# MSP.net
KiCad netlist of a schematic drawn in Altium Designer
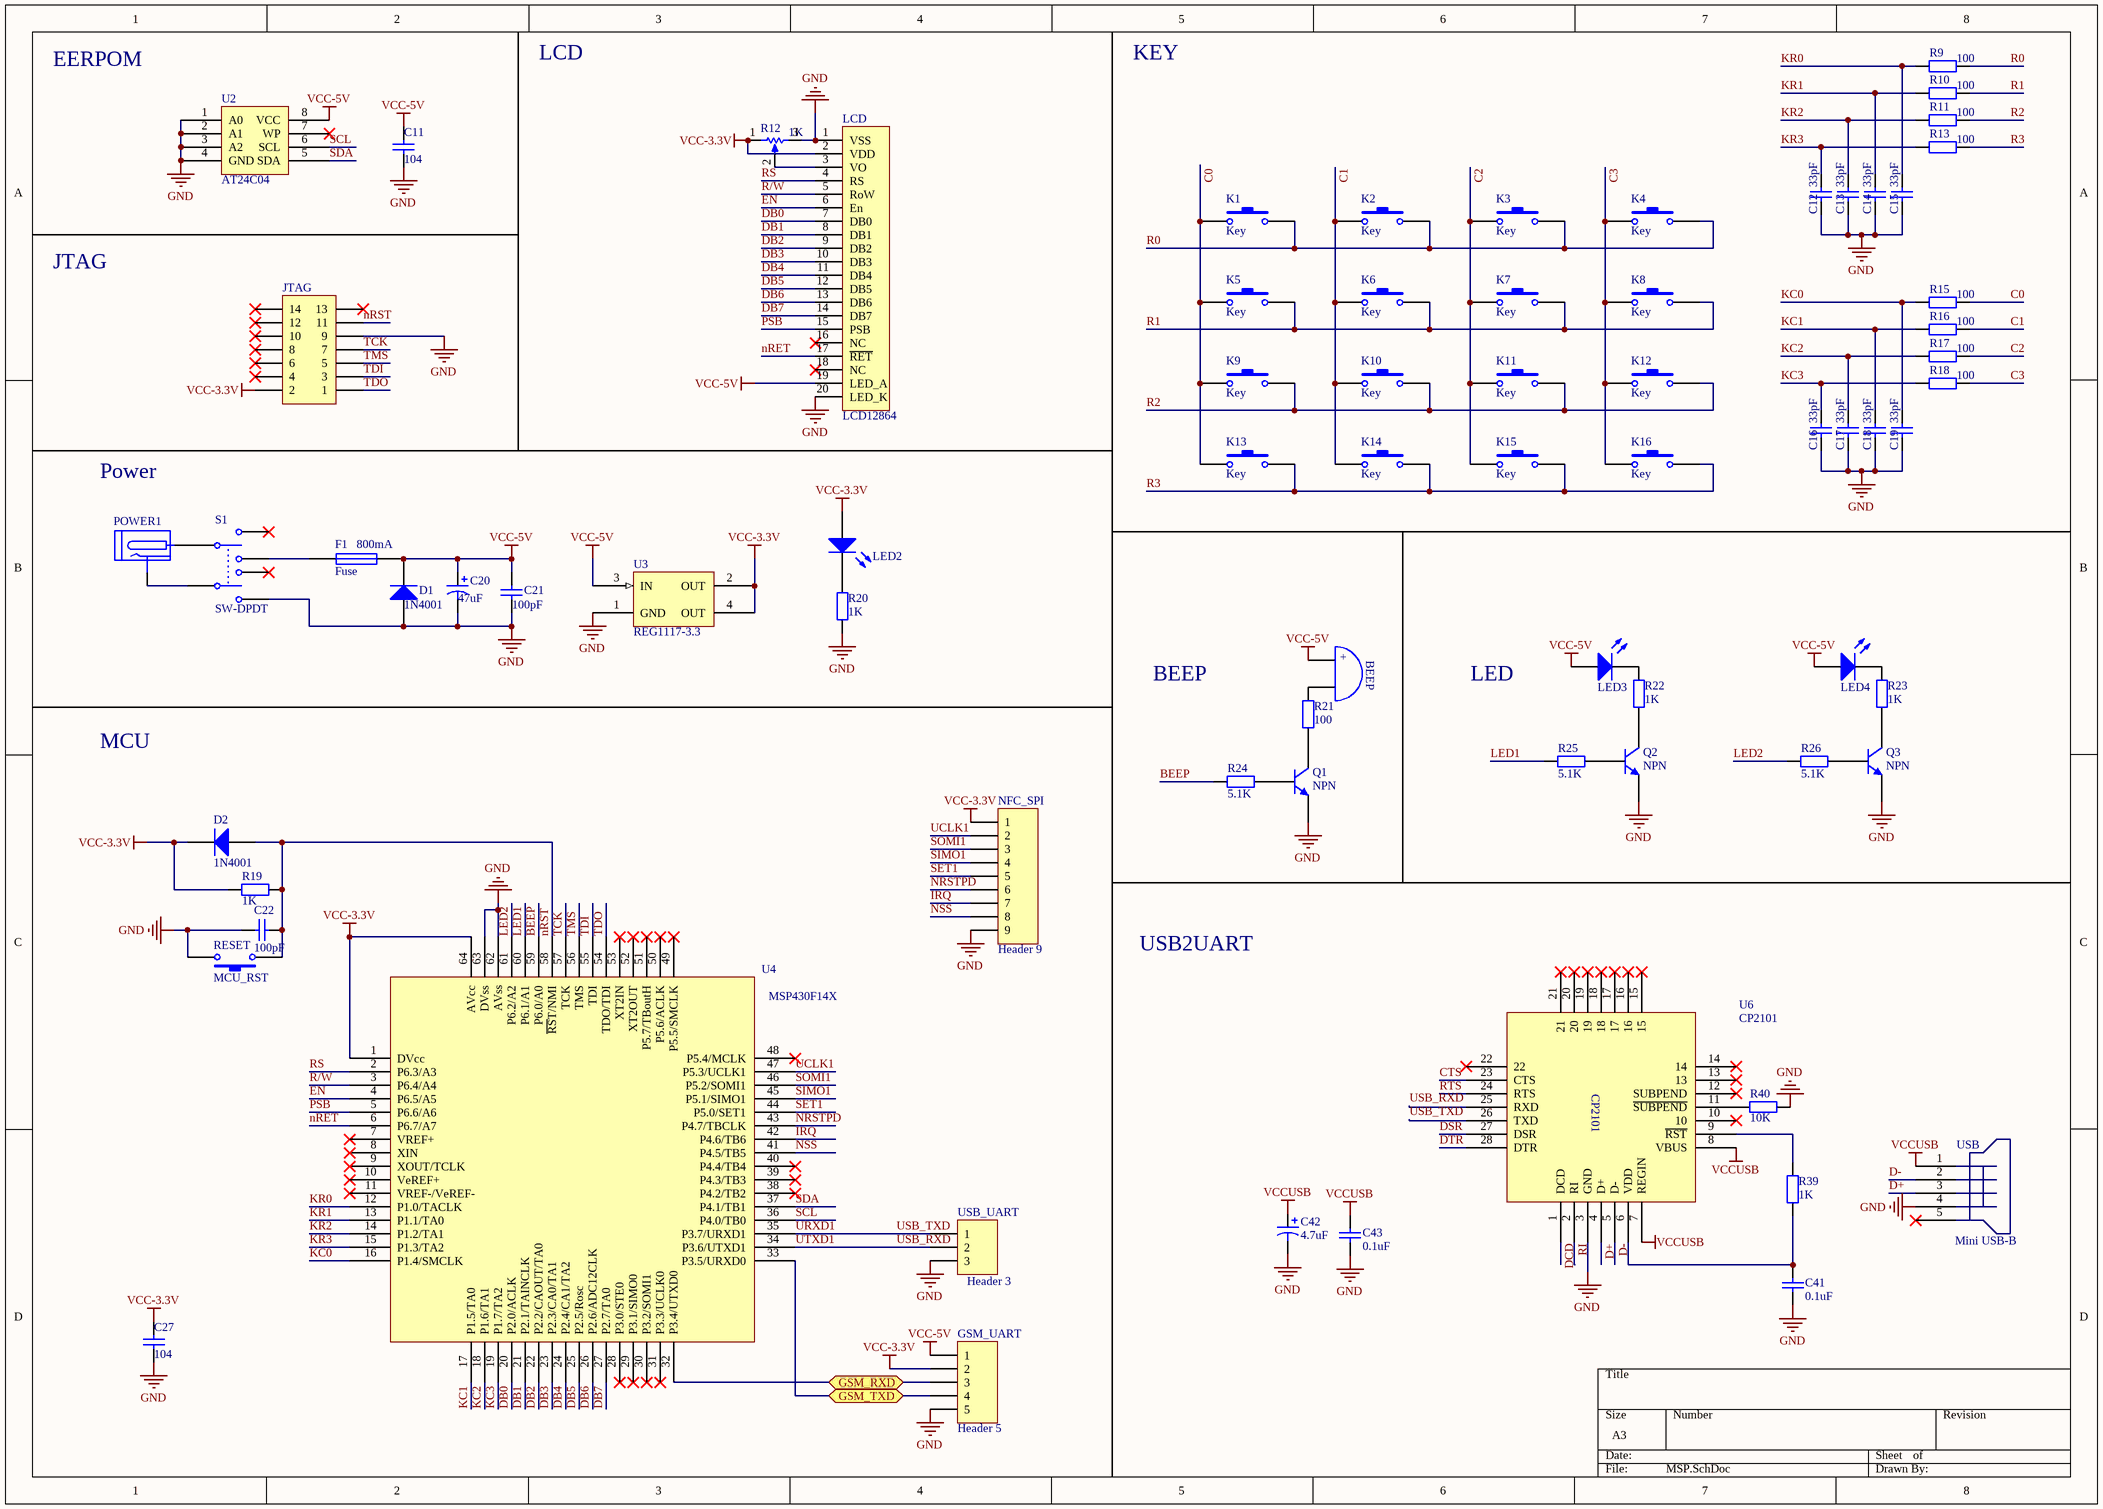
[diagram p0: MSP.SchDoc]

(export (version "E")
  (design (tool "Eeschema 10.0.6"))
  (components
    (comp (ref "BEEP1") (value "BEEP") (footprint "BEEP") (libsource (lib "common") (part "BEEP")))
    (comp (ref "C11")
      (value "104")
      (footprint "1608[0603]")
      (description "Capacitor")
      (fields (field (name "Comment") "Cap") (field (name "PUBLISHER") "Altium Limited"))
      (libsource (lib "common") (part "Cap"))
    )
    (comp (ref "C12")
      (value "33pF")
      (footprint "1608[0603]")
      (description "Capacitor")
      (fields (field (name "Comment") "Cap") (field (name "PUBLISHER") "Altium Limited"))
      (libsource (lib "common") (part "Cap"))
    )
    (comp (ref "C13")
      (value "33pF")
      (footprint "1608[0603]")
      (description "Capacitor")
      (fields (field (name "Comment") "Cap") (field (name "PUBLISHER") "Altium Limited"))
      (libsource (lib "common") (part "Cap"))
    )
    (comp (ref "C14")
      (value "33pF")
      (footprint "1608[0603]")
      (description "Capacitor")
      (fields (field (name "Comment") "Cap") (field (name "PUBLISHER") "Altium Limited"))
      (libsource (lib "common") (part "Cap"))
    )
    (comp (ref "C15")
      (value "33pF")
      (footprint "1608[0603]")
      (description "Capacitor")
      (fields (field (name "Comment") "Cap") (field (name "PUBLISHER") "Altium Limited"))
      (libsource (lib "common") (part "Cap"))
    )
    (comp (ref "C16")
      (value "33pF")
      (footprint "1608[0603]")
      (description "Capacitor")
      (fields (field (name "Comment") "Cap") (field (name "PUBLISHER") "Altium Limited"))
      (libsource (lib "common") (part "Cap"))
    )
    (comp (ref "C17")
      (value "33pF")
      (footprint "1608[0603]")
      (description "Capacitor")
      (fields (field (name "Comment") "Cap") (field (name "PUBLISHER") "Altium Limited"))
      (libsource (lib "common") (part "Cap"))
    )
    (comp (ref "C18")
      (value "33pF")
      (footprint "1608[0603]")
      (description "Capacitor")
      (fields (field (name "Comment") "Cap") (field (name "PUBLISHER") "Altium Limited"))
      (libsource (lib "common") (part "Cap"))
    )
    (comp (ref "C19")
      (value "33pF")
      (footprint "1608[0603]")
      (description "Capacitor")
      (fields (field (name "Comment") "Cap") (field (name "PUBLISHER") "Altium Limited"))
      (libsource (lib "common") (part "Cap"))
    )
    (comp (ref "C20")
      (value "47uF")
      (footprint "Standard:B")
      (description "Polarized Capacitor (Axial)")
      (fields (field (name "Comment") "CAP POL") (field (name "PUBLISHER") "Altium Limited"))
      (libsource (lib "common") (part "CAP POL"))
    )
    (comp (ref "C21")
      (value "100pF")
      (footprint "1608[0603]")
      (description "Capacitor")
      (fields (field (name "Comment") "Cap") (field (name "PUBLISHER") "Altium Limited"))
      (libsource (lib "common") (part "Cap"))
    )
    (comp (ref "C22")
      (value "100pF")
      (footprint "1608[0603]")
      (description "Capacitor")
      (fields (field (name "Comment") "Cap") (field (name "PUBLISHER") "Altium Limited"))
      (libsource (lib "common") (part "Cap"))
    )
    (comp (ref "C27")
      (value "104")
      (footprint "1608[0603]")
      (description "Capacitor")
      (fields (field (name "Comment") "Cap") (field (name "PUBLISHER") "Altium Limited"))
      (libsource (lib "common") (part "Cap"))
    )
    (comp (ref "C41")
      (value "0.1uF")
      (footprint "1608[0603]")
      (description "Capacitor")
      (fields (field (name "Comment") "Cap") (field (name "PUBLISHER") "Altium Limited"))
      (libsource (lib "common") (part "Cap"))
    )
    (comp (ref "C42")
      (value "4.7uF")
      (footprint "Standard:B")
      (description "Polarized Capacitor (Axial)")
      (fields (field (name "Comment") "CAP POL") (field (name "PUBLISHER") "Altium Limited"))
      (libsource (lib "common") (part "CAP POL"))
    )
    (comp (ref "C43")
      (value "0.1uF")
      (footprint "1608[0603]")
      (description "Capacitor")
      (fields (field (name "Comment") "Cap") (field (name "PUBLISHER") "Altium Limited"))
      (libsource (lib "common") (part "Cap"))
    )
    (comp (ref "D1")
      (value "1N4001")
      (footprint "1608[0603] - POL")
      (description "1 Amp General Purpose Rectifier")
      (fields (field (name "PUBLISHER") "Altium Limited"))
      (libsource (lib "common") (part "Diode 1N4001"))
    )
    (comp (ref "D2")
      (value "1N4001")
      (footprint "1608[0603] - POL")
      (description "1 Amp General Purpose Rectifier")
      (fields (field (name "PUBLISHER") "Altium Limited"))
      (libsource (lib "common") (part "Diode 1N4001"))
    )
    (comp (ref "F1")
      (value "Fuse")
      (footprint "2012[0805]")
      (fields (field (name "CURRENT") "800mA"))
      (libsource (lib "common") (part "FUSE1"))
    )
    (comp (ref "GSM_UART")
      (value "Header 5")
      (footprint "HDR1X5")
      (description "Header, 5-Pin")
      (fields (field (name "PUBLISHER") "Altium Limited"))
      (libsource (lib "Miscellaneous Connectors") (part "Header 5"))
    )
    (comp (ref "JTAG")
      (value "Header 7X2H")
      (footprint "HDR2X7H")
      (description "Header, 7-Pin, Dual row, Right Angle")
      (fields (field (name "PUBLISHER") "Altium Limited"))
      (libsource (lib "Miscellaneous Connectors") (part "Header 7X2H"))
    )
    (comp (ref "K1") (value "Key") (footprint "Key-4") (libsource (lib "*") (part "SW-PB")))
    (comp (ref "K2") (value "Key") (footprint "Key-4") (libsource (lib "common") (part "SW-PB")))
    (comp (ref "K3") (value "Key") (footprint "Key-4") (libsource (lib "common") (part "SW-PB")))
    (comp (ref "K4") (value "Key") (footprint "Key-4") (libsource (lib "common") (part "SW-PB")))
    (comp (ref "K5") (value "Key") (footprint "Key-4") (libsource (lib "common") (part "SW-PB")))
    (comp (ref "K6") (value "Key") (footprint "Key-4") (libsource (lib "common") (part "SW-PB")))
    (comp (ref "K7") (value "Key") (footprint "Key-4") (libsource (lib "common") (part "SW-PB")))
    (comp (ref "K8") (value "Key") (footprint "Key-4") (libsource (lib "common") (part "SW-PB")))
    (comp (ref "K9") (value "Key") (footprint "Key-4") (libsource (lib "common") (part "SW-PB")))
    (comp (ref "K10") (value "Key") (footprint "Key-4") (libsource (lib "common") (part "SW-PB")))
    (comp (ref "K11") (value "Key") (footprint "Key-4") (libsource (lib "common") (part "SW-PB")))
    (comp (ref "K12") (value "Key") (footprint "Key-4") (libsource (lib "common") (part "SW-PB")))
    (comp (ref "K13") (value "Key") (footprint "Key-4") (libsource (lib "common") (part "SW-PB")))
    (comp (ref "K14") (value "Key") (footprint "Key-4") (libsource (lib "common") (part "SW-PB")))
    (comp (ref "K15") (value "Key") (footprint "Key-4") (libsource (lib "common") (part "SW-PB")))
    (comp (ref "K16") (value "Key") (footprint "Key-4") (libsource (lib "common") (part "SW-PB")))
    (comp (ref "LCD") (value "LCD12864") (footprint "LCD-20PIN") (libsource (lib "*") (part "LCD12864")))
    (comp (ref "LED2") (value "LED") (footprint "2012[0805] - POL") (libsource (lib "common") (part "LED")))
    (comp (ref "LED3") (value "LED") (footprint "2012[0805] - POL") (libsource (lib "common") (part "LED")))
    (comp (ref "LED4") (value "LED") (footprint "2012[0805] - POL") (libsource (lib "common") (part "LED")))
    (comp (ref "NFC_SPI")
      (value "Header 9")
      (footprint "HDR1X9")
      (description "Header, 9-Pin")
      (fields (field (name "PUBLISHER") "Altium Limited"))
      (libsource (lib "Miscellaneous Connectors") (part "Header 9"))
    )
    (comp (ref "POWER1") (value "POWER") (footprint "POWER") (libsource (lib "51ExpBoard") (part "POWER")))
    (comp (ref "Q1") (value "NPN") (footprint "SOT23-3L") (libsource (lib "common") (part "NPN")))
    (comp (ref "Q2") (value "NPN") (footprint "SOT23-3L") (libsource (lib "common") (part "NPN")))
    (comp (ref "Q3") (value "NPN") (footprint "SOT23-3L") (libsource (lib "common") (part "NPN")))
    (comp (ref "R9")
      (value "100")
      (footprint "1608[0603]")
      (description "Resistor")
      (fields (field (name "Comment") "RES") (field (name "PUBLISHER") "Altium Limited"))
      (libsource (lib "") (part "RES_1"))
    )
    (comp (ref "R10")
      (value "100")
      (footprint "1608[0603]")
      (description "Resistor")
      (fields (field (name "Comment") "RES") (field (name "PUBLISHER") "Altium Limited"))
      (libsource (lib "") (part "RES_1"))
    )
    (comp (ref "R11")
      (value "100")
      (footprint "1608[0603]")
      (description "Resistor")
      (fields (field (name "Comment") "RES") (field (name "PUBLISHER") "Altium Limited"))
      (libsource (lib "") (part "RES_1"))
    )
    (comp (ref "R12")
      (value "1K")
      (footprint "VR5")
      (description "Potentiometer")
      (fields (field (name "Comment") "RPot") (field (name "PUBLISHER") "Altium Limited"))
      (libsource (lib "Miscellaneous Devices") (part "RPot"))
    )
    (comp (ref "R13")
      (value "100")
      (footprint "1608[0603]")
      (description "Resistor")
      (fields (field (name "Comment") "RES") (field (name "PUBLISHER") "Altium Limited"))
      (libsource (lib "") (part "RES_1"))
    )
    (comp (ref "R15")
      (value "100")
      (footprint "1608[0603]")
      (description "Resistor")
      (fields (field (name "Comment") "RES") (field (name "PUBLISHER") "Altium Limited"))
      (libsource (lib "") (part "RES_1"))
    )
    (comp (ref "R16")
      (value "100")
      (footprint "1608[0603]")
      (description "Resistor")
      (fields (field (name "Comment") "RES") (field (name "PUBLISHER") "Altium Limited"))
      (libsource (lib "") (part "RES_1"))
    )
    (comp (ref "R17")
      (value "100")
      (footprint "1608[0603]")
      (description "Resistor")
      (fields (field (name "Comment") "RES") (field (name "PUBLISHER") "Altium Limited"))
      (libsource (lib "") (part "RES_1"))
    )
    (comp (ref "R18")
      (value "100")
      (footprint "1608[0603]")
      (description "Resistor")
      (fields (field (name "Comment") "RES") (field (name "PUBLISHER") "Altium Limited"))
      (libsource (lib "") (part "RES_1"))
    )
    (comp (ref "R19")
      (value "1K")
      (footprint "1608[0603]")
      (description "Resistor")
      (fields (field (name "Comment") "Res") (field (name "PUBLISHER") "Altium Limited"))
      (libsource (lib "") (part "RES_3"))
    )
    (comp (ref "R20")
      (value "1K")
      (footprint "1608[0603]")
      (description "Resistor")
      (fields (field (name "Comment") "Res") (field (name "PUBLISHER") "Altium Limited"))
      (libsource (lib "common") (part "RES"))
    )
    (comp (ref "R21")
      (value "100")
      (footprint "1608[0603]")
      (description "Resistor")
      (fields (field (name "Comment") "Res") (field (name "PUBLISHER") "Altium Limited"))
      (libsource (lib "common") (part "RES"))
    )
    (comp (ref "R22")
      (value "1K")
      (footprint "1608[0603]")
      (description "Resistor")
      (fields (field (name "Comment") "Res") (field (name "PUBLISHER") "Altium Limited"))
      (libsource (lib "common") (part "RES"))
    )
    (comp (ref "R23")
      (value "1K")
      (footprint "1608[0603]")
      (description "Resistor")
      (fields (field (name "Comment") "Res") (field (name "PUBLISHER") "Altium Limited"))
      (libsource (lib "common") (part "RES"))
    )
    (comp (ref "R24")
      (value "5.1K")
      (footprint "1608[0603]")
      (description "Resistor")
      (fields (field (name "Comment") "Res") (field (name "PUBLISHER") "Altium Limited"))
      (libsource (lib "") (part "RES_1"))
    )
    (comp (ref "R25")
      (value "5.1K")
      (footprint "1608[0603]")
      (description "Resistor")
      (fields (field (name "Comment") "Res") (field (name "PUBLISHER") "Altium Limited"))
      (libsource (lib "") (part "RES_1"))
    )
    (comp (ref "R26")
      (value "5.1K")
      (footprint "1608[0603]")
      (description "Resistor")
      (fields (field (name "Comment") "Res") (field (name "PUBLISHER") "Altium Limited"))
      (libsource (lib "") (part "RES_1"))
    )
    (comp (ref "R39")
      (value "1K")
      (footprint "1608[0603]")
      (description "Resistor")
      (fields (field (name "Comment") "Res") (field (name "PUBLISHER") "Altium Limited"))
      (libsource (lib "") (part "RES_2"))
    )
    (comp (ref "R40")
      (value "10K")
      (footprint "1608[0603]")
      (description "Resistor")
      (fields (field (name "Comment") "Res") (field (name "PUBLISHER") "Altium Limited"))
      (libsource (lib "") (part "RES_1"))
    )
    (comp (ref "RESET") (value "MCU_RST") (footprint "Key-4") (libsource (lib "common") (part "SW-PB")))
    (comp (ref "S1")
      (value "SW-DPDT")
      (footprint "SW-DPDT")
      (description "Double-Pole, Double-Throw Switch")
      (fields (field (name "PUBLISHER") "Altium Limited"))
      (libsource (lib "common") (part "SW-DPDT"))
    )
    (comp (ref "U2")
      (value "AT24C04")
      (footprint "SOIC127P600-8AN")
      (libsource (lib "common") (part "AT24C04"))
    )
    (comp (ref "U3")
      (value "REG1117-3.3")
      (footprint "SOT223")
      (libsource (lib "MYSELF") (part "REG1117-3.3"))
    )
    (comp (ref "U4")
      (value "MSP430F14X")
      (footprint "SQFP50P1200X1200-64N")
      (libsource (lib "*") (part "MSP430F14X"))
    )
    (comp (ref "U6")
      (value "CP2101")
      (footprint "QFN50P500X500-28VAN")
      (libsource (lib "USB2UART") (part "CP2101"))
    )
    (comp (ref "USB")
      (value "Mini USB-B")
      (footprint "Mini USB-400")
      (description "Mini USB Type B")
      (libsource (lib "USB2UART") (part "USB"))
    )
    (comp (ref "USB_UART")
      (value "Header 3")
      (footprint "HDR1X3")
      (description "Header, 3-Pin")
      (fields (field (name "PUBLISHER") "Altium Limited"))
      (libsource (lib "Miscellaneous Connectors") (part "Header 3"))
    )
  )
  (nets
    (net (code "1") (name "/BEEP") (class "Default")
      (node (ref "R24") (pin "1") (pinfunction "1_1") (pintype "passive"))
      (node (ref "U4") (pin "59") (pinfunction "P6.0/A0_59") (pintype "power_in"))
    )
    (net (code "2") (name "/C0") (class "Default")
      (node (ref "K1") (pin "1") (pinfunction "1_1") (pintype "passive"))
      (node (ref "K13") (pin "1") (pinfunction "1_1") (pintype "passive"))
      (node (ref "K5") (pin "1") (pinfunction "1_1") (pintype "passive"))
      (node (ref "K9") (pin "1") (pinfunction "1_1") (pintype "passive"))
      (node (ref "R15") (pin "2") (pinfunction "2_2") (pintype "passive"))
    )
    (net (code "3") (name "/C1") (class "Default")
      (node (ref "K10") (pin "1") (pinfunction "1_1") (pintype "passive"))
      (node (ref "K14") (pin "1") (pinfunction "1_1") (pintype "passive"))
      (node (ref "K2") (pin "1") (pinfunction "1_1") (pintype "passive"))
      (node (ref "K6") (pin "1") (pinfunction "1_1") (pintype "passive"))
      (node (ref "R16") (pin "2") (pinfunction "2_2") (pintype "passive"))
    )
    (net (code "4") (name "/C2") (class "Default")
      (node (ref "K11") (pin "1") (pinfunction "1_1") (pintype "passive"))
      (node (ref "K15") (pin "1") (pinfunction "1_1") (pintype "passive"))
      (node (ref "K3") (pin "1") (pinfunction "1_1") (pintype "passive"))
      (node (ref "K7") (pin "1") (pinfunction "1_1") (pintype "passive"))
      (node (ref "R17") (pin "2") (pinfunction "2_2") (pintype "passive"))
    )
    (net (code "5") (name "/C3") (class "Default")
      (node (ref "K12") (pin "1") (pinfunction "1_1") (pintype "passive"))
      (node (ref "K16") (pin "1") (pinfunction "1_1") (pintype "passive"))
      (node (ref "K4") (pin "1") (pinfunction "1_1") (pintype "passive"))
      (node (ref "K8") (pin "1") (pinfunction "1_1") (pintype "passive"))
      (node (ref "R18") (pin "2") (pinfunction "2_2") (pintype "passive"))
    )
    (net (code "6") (name "/CTS") (class "Default")
      (node (ref "U6") (pin "23") (pinfunction "CTS_23") (pintype "passive"))
    )
    (net (code "7") (name "/D+") (class "Default")
      (node (ref "U6") (pin "4") (pinfunction "D+_4") (pintype "passive"))
      (node (ref "USB") (pin "3") (pinfunction "3_3") (pintype "passive"))
    )
    (net (code "8") (name "/D-") (class "Default")
      (node (ref "U6") (pin "5") (pinfunction "D-_5") (pintype "passive"))
      (node (ref "USB") (pin "2") (pinfunction "2_2") (pintype "passive"))
    )
    (net (code "9") (name "/DB0") (class "Default")
      (node (ref "LCD") (pin "7") (pinfunction "DB0_7") (pintype "passive"))
      (node (ref "U4") (pin "20") (pinfunction "P2.0/ACLK_20") (pintype "power_in"))
    )
    (net (code "10") (name "/DB1") (class "Default")
      (node (ref "LCD") (pin "8") (pinfunction "DB1_8") (pintype "passive"))
      (node (ref "U4") (pin "21") (pinfunction "P2.1/TAINCLK_21") (pintype "power_in"))
    )
    (net (code "11") (name "/DB2") (class "Default")
      (node (ref "LCD") (pin "9") (pinfunction "DB2_9") (pintype "passive"))
      (node (ref "U4") (pin "22") (pinfunction "P2.2/CAOUT/TA0_22") (pintype "power_in"))
    )
    (net (code "12") (name "/DB3") (class "Default")
      (node (ref "LCD") (pin "10") (pinfunction "DB3_10") (pintype "passive"))
      (node (ref "U4") (pin "23") (pinfunction "P2.3/CA0/TA1_23") (pintype "power_in"))
    )
    (net (code "13") (name "/DB4") (class "Default")
      (node (ref "LCD") (pin "11") (pinfunction "DB4_11") (pintype "passive"))
      (node (ref "U4") (pin "24") (pinfunction "P2.4/CA1/TA2_24") (pintype "power_in"))
    )
    (net (code "14") (name "/DB5") (class "Default")
      (node (ref "LCD") (pin "12") (pinfunction "DB5_12") (pintype "passive"))
      (node (ref "U4") (pin "25") (pinfunction "P2.5/Rosc_25") (pintype "power_in"))
    )
    (net (code "15") (name "/DB6") (class "Default")
      (node (ref "LCD") (pin "13") (pinfunction "DB6_13") (pintype "passive"))
      (node (ref "U4") (pin "26") (pinfunction "P2.6/ADC12CLK_26") (pintype "power_in"))
    )
    (net (code "16") (name "/DB7") (class "Default")
      (node (ref "LCD") (pin "14") (pinfunction "DB7_14") (pintype "passive"))
      (node (ref "U4") (pin "27") (pinfunction "P2.7/TA0_27") (pintype "power_in"))
    )
    (net (code "17") (name "/DCD") (class "Default")
      (node (ref "U6") (pin "1") (pinfunction "DCD_1") (pintype "passive"))
    )
    (net (code "18") (name "/DSR") (class "Default")
      (node (ref "U6") (pin "27") (pinfunction "DSR_27") (pintype "passive"))
    )
    (net (code "19") (name "/DTR") (class "Default")
      (node (ref "U6") (pin "28") (pinfunction "DTR_28") (pintype "passive"))
    )
    (net (code "20") (name "/EN") (class "Default")
      (node (ref "LCD") (pin "6") (pinfunction "En_6") (pintype "passive"))
      (node (ref "U4") (pin "4") (pinfunction "P6.5/A5_4") (pintype "power_in"))
    )
    (net (code "21") (name "/GSM_RXD") (class "Default")
      (node (ref "GSM_UART") (pin "3") (pinfunction "3_3") (pintype "passive"))
      (node (ref "U4") (pin "32") (pinfunction "P3.4/UTXD0_32") (pintype "power_in"))
    )
    (net (code "22") (name "/GSM_TXD") (class "Default")
      (node (ref "GSM_UART") (pin "4") (pinfunction "4_4") (pintype "passive"))
      (node (ref "U4") (pin "33") (pinfunction "P3.5/URXD0_33") (pintype "power_in"))
    )
    (net (code "23") (name "/IRQ") (class "Default")
      (node (ref "NFC_SPI") (pin "7") (pinfunction "7_7") (pintype "passive"))
      (node (ref "U4") (pin "42") (pinfunction "P4.6/TB6_42") (pintype "power_in"))
    )
    (net (code "24") (name "/KC0") (class "Default")
      (node (ref "C19") (pin "1") (pinfunction "1_1") (pintype "passive"))
      (node (ref "R15") (pin "1") (pinfunction "1_1") (pintype "passive"))
      (node (ref "U4") (pin "16") (pinfunction "P1.4/SMCLK_16") (pintype "power_in"))
    )
    (net (code "25") (name "/KC1") (class "Default")
      (node (ref "C18") (pin "1") (pinfunction "1_1") (pintype "passive"))
      (node (ref "R16") (pin "1") (pinfunction "1_1") (pintype "passive"))
      (node (ref "U4") (pin "17") (pinfunction "P1.5/TA0_17") (pintype "power_in"))
    )
    (net (code "26") (name "/KC2") (class "Default")
      (node (ref "C17") (pin "1") (pinfunction "1_1") (pintype "passive"))
      (node (ref "R17") (pin "1") (pinfunction "1_1") (pintype "passive"))
      (node (ref "U4") (pin "18") (pinfunction "P1.6/TA1_18") (pintype "power_in"))
    )
    (net (code "27") (name "/KC3") (class "Default")
      (node (ref "C16") (pin "1") (pinfunction "1_1") (pintype "passive"))
      (node (ref "R18") (pin "1") (pinfunction "1_1") (pintype "passive"))
      (node (ref "U4") (pin "19") (pinfunction "P1.7/TA2_19") (pintype "power_in"))
    )
    (net (code "28") (name "/KR0") (class "Default")
      (node (ref "C15") (pin "1") (pinfunction "1_1") (pintype "passive"))
      (node (ref "R9") (pin "1") (pinfunction "1_1") (pintype "passive"))
      (node (ref "U4") (pin "12") (pinfunction "P1.0/TACLK_12") (pintype "power_in"))
    )
    (net (code "29") (name "/KR1") (class "Default")
      (node (ref "C14") (pin "1") (pinfunction "1_1") (pintype "passive"))
      (node (ref "R10") (pin "1") (pinfunction "1_1") (pintype "passive"))
      (node (ref "U4") (pin "13") (pinfunction "P1.1/TA0_13") (pintype "power_in"))
    )
    (net (code "30") (name "/KR2") (class "Default")
      (node (ref "C13") (pin "1") (pinfunction "1_1") (pintype "passive"))
      (node (ref "R11") (pin "1") (pinfunction "1_1") (pintype "passive"))
      (node (ref "U4") (pin "14") (pinfunction "P1.2/TA1_14") (pintype "power_in"))
    )
    (net (code "31") (name "/KR3") (class "Default")
      (node (ref "C12") (pin "1") (pinfunction "1_1") (pintype "passive"))
      (node (ref "R13") (pin "1") (pinfunction "1_1") (pintype "passive"))
      (node (ref "U4") (pin "15") (pinfunction "P1.3/TA2_15") (pintype "power_in"))
    )
    (net (code "32") (name "/LED1") (class "Default")
      (node (ref "R25") (pin "1") (pinfunction "1_1") (pintype "passive"))
      (node (ref "U4") (pin "60") (pinfunction "P6.1/A1_60") (pintype "power_in"))
    )
    (net (code "33") (name "/LED2") (class "Default")
      (node (ref "R26") (pin "1") (pinfunction "1_1") (pintype "passive"))
      (node (ref "U4") (pin "61") (pinfunction "P6.2/A2_61") (pintype "power_in"))
    )
    (net (code "34") (name "/NRSTPD") (class "Default")
      (node (ref "NFC_SPI") (pin "6") (pinfunction "6_6") (pintype "passive"))
      (node (ref "U4") (pin "43") (pinfunction "P4.7/TBCLK_43") (pintype "power_in"))
    )
    (net (code "35") (name "/NSS") (class "Default")
      (node (ref "NFC_SPI") (pin "8") (pinfunction "8_8") (pintype "passive"))
      (node (ref "U4") (pin "41") (pinfunction "P4.5/TB5_41") (pintype "power_in"))
    )
    (net (code "36") (name "/PSB") (class "Default")
      (node (ref "LCD") (pin "15") (pinfunction "PSB_15") (pintype "passive"))
      (node (ref "U4") (pin "5") (pinfunction "P6.6/A6_5") (pintype "power_in"))
    )
    (net (code "37") (name "/R0") (class "Default")
      (node (ref "K1") (pin "2") (pinfunction "2_2") (pintype "passive"))
      (node (ref "K2") (pin "2") (pinfunction "2_2") (pintype "passive"))
      (node (ref "K3") (pin "2") (pinfunction "2_2") (pintype "passive"))
      (node (ref "K4") (pin "2") (pinfunction "2_2") (pintype "passive"))
      (node (ref "R9") (pin "2") (pinfunction "2_2") (pintype "passive"))
    )
    (net (code "38") (name "/R1") (class "Default")
      (node (ref "K5") (pin "2") (pinfunction "2_2") (pintype "passive"))
      (node (ref "K6") (pin "2") (pinfunction "2_2") (pintype "passive"))
      (node (ref "K7") (pin "2") (pinfunction "2_2") (pintype "passive"))
      (node (ref "K8") (pin "2") (pinfunction "2_2") (pintype "passive"))
      (node (ref "R10") (pin "2") (pinfunction "2_2") (pintype "passive"))
    )
    (net (code "39") (name "/R2") (class "Default")
      (node (ref "K10") (pin "2") (pinfunction "2_2") (pintype "passive"))
      (node (ref "K11") (pin "2") (pinfunction "2_2") (pintype "passive"))
      (node (ref "K12") (pin "2") (pinfunction "2_2") (pintype "passive"))
      (node (ref "K9") (pin "2") (pinfunction "2_2") (pintype "passive"))
      (node (ref "R11") (pin "2") (pinfunction "2_2") (pintype "passive"))
    )
    (net (code "40") (name "/R3") (class "Default")
      (node (ref "K13") (pin "2") (pinfunction "2_2") (pintype "passive"))
      (node (ref "K14") (pin "2") (pinfunction "2_2") (pintype "passive"))
      (node (ref "K15") (pin "2") (pinfunction "2_2") (pintype "passive"))
      (node (ref "K16") (pin "2") (pinfunction "2_2") (pintype "passive"))
      (node (ref "R13") (pin "2") (pinfunction "2_2") (pintype "passive"))
    )
    (net (code "41") (name "/RI") (class "Default")
      (node (ref "U6") (pin "2") (pinfunction "RI_2") (pintype "passive"))
    )
    (net (code "42") (name "/RS") (class "Default")
      (node (ref "LCD") (pin "4") (pinfunction "RS_4") (pintype "passive"))
      (node (ref "U4") (pin "2") (pinfunction "P6.3/A3_2") (pintype "power_in"))
    )
    (net (code "43") (name "/RTS") (class "Default")
      (node (ref "U6") (pin "24") (pinfunction "RTS_24") (pintype "passive"))
    )
    (net (code "44") (name "/R{slash}W") (class "Default")
      (node (ref "LCD") (pin "5") (pinfunction "RoW_5") (pintype "passive"))
      (node (ref "U4") (pin "3") (pinfunction "P6.4/A4_3") (pintype "power_in"))
    )
    (net (code "45") (name "/SCL") (class "Default")
      (node (ref "U2") (pin "6") (pinfunction "SCL_6") (pintype "passive"))
      (node (ref "U4") (pin "36") (pinfunction "P4.0/TB0_36") (pintype "power_in"))
    )
    (net (code "46") (name "/SDA") (class "Default")
      (node (ref "U2") (pin "5") (pinfunction "SDA_5") (pintype "passive"))
      (node (ref "U4") (pin "37") (pinfunction "P4.1/TB1_37") (pintype "power_in"))
    )
    (net (code "47") (name "/SET1") (class "Default")
      (node (ref "NFC_SPI") (pin "5") (pinfunction "5_5") (pintype "passive"))
      (node (ref "U4") (pin "44") (pinfunction "P5.0/SET1_44") (pintype "power_in"))
    )
    (net (code "48") (name "/SIMO1") (class "Default")
      (node (ref "NFC_SPI") (pin "4") (pinfunction "4_4") (pintype "passive"))
      (node (ref "U4") (pin "45") (pinfunction "P5.1/SIMO1_45") (pintype "power_in"))
    )
    (net (code "49") (name "/SOMI1") (class "Default")
      (node (ref "NFC_SPI") (pin "3") (pinfunction "3_3") (pintype "passive"))
      (node (ref "U4") (pin "46") (pinfunction "P5.2/SOMI1_46") (pintype "power_in"))
    )
    (net (code "50") (name "/TCK") (class "Default")
      (node (ref "JTAG") (pin "7") (pinfunction "7_7") (pintype "passive"))
      (node (ref "U4") (pin "57") (pinfunction "TCK_57") (pintype "power_in"))
    )
    (net (code "51") (name "/TDI") (class "Default")
      (node (ref "JTAG") (pin "3") (pinfunction "3_3") (pintype "passive"))
      (node (ref "U4") (pin "55") (pinfunction "TDI_55") (pintype "power_in"))
    )
    (net (code "52") (name "/TDO") (class "Default")
      (node (ref "JTAG") (pin "1") (pinfunction "1_1") (pintype "passive"))
      (node (ref "U4") (pin "54") (pinfunction "TDO/TDI_54") (pintype "power_in"))
    )
    (net (code "53") (name "/TMS") (class "Default")
      (node (ref "JTAG") (pin "5") (pinfunction "5_5") (pintype "passive"))
      (node (ref "U4") (pin "56") (pinfunction "TMS_56") (pintype "power_in"))
    )
    (net (code "54") (name "/UCLK1") (class "Default")
      (node (ref "NFC_SPI") (pin "2") (pinfunction "2_2") (pintype "passive"))
      (node (ref "U4") (pin "47") (pinfunction "P5.3/UCLK1_47") (pintype "power_in"))
    )
    (net (code "55") (name "/URXD1") (class "Default")
      (node (ref "U4") (pin "35") (pinfunction "P3.7/URXD1_35") (pintype "power_in"))
      (node (ref "U6") (pin "26") (pinfunction "TXD_26") (pintype "passive"))
      (node (ref "USB_UART") (pin "1") (pinfunction "1_1") (pintype "passive"))
    )
    (net (code "56") (name "/USB_RXD") (class "Default")
      (node (ref "U4") (pin "34") (pinfunction "P3.6/UTXD1_34") (pintype "power_in"))
      (node (ref "U6") (pin "25") (pinfunction "RXD_25") (pintype "passive"))
      (node (ref "USB_UART") (pin "2") (pinfunction "2_2") (pintype "passive"))
    )
    (net (code "57") (name "/nRET") (class "Default")
      (node (ref "LCD") (pin "17") (pinfunction "~{RET}_17") (pintype "passive"))
      (node (ref "U4") (pin "6") (pinfunction "P6.7/A7_6") (pintype "power_in"))
    )
    (net (code "58") (name "/nRST") (class "Default")
      (node (ref "C22") (pin "1") (pinfunction "1_1") (pintype "passive"))
      (node (ref "D2") (pin "1") (pinfunction "A_1") (pintype "passive"))
      (node (ref "JTAG") (pin "11") (pinfunction "11_11") (pintype "passive"))
      (node (ref "R19") (pin "1") (pinfunction "1_1") (pintype "passive"))
      (node (ref "RESET") (pin "1") (pinfunction "1_1") (pintype "passive"))
      (node (ref "U4") (pin "58") (pinfunction "~{RS}T/NMI_58") (pintype "power_in"))
    )
    (net (code "59") (name "GND") (class "Default")
      (node (ref "C11") (pin "1") (pinfunction "1_1") (pintype "passive"))
      (node (ref "C12") (pin "2") (pinfunction "2_2") (pintype "passive"))
      (node (ref "C13") (pin "2") (pinfunction "2_2") (pintype "passive"))
      (node (ref "C14") (pin "2") (pinfunction "2_2") (pintype "passive"))
      (node (ref "C15") (pin "2") (pinfunction "2_2") (pintype "passive"))
      (node (ref "C16") (pin "2") (pinfunction "2_2") (pintype "passive"))
      (node (ref "C17") (pin "2") (pinfunction "2_2") (pintype "passive"))
      (node (ref "C18") (pin "2") (pinfunction "2_2") (pintype "passive"))
      (node (ref "C19") (pin "2") (pinfunction "2_2") (pintype "passive"))
      (node (ref "C20") (pin "2") (pinfunction "2_2") (pintype "passive"))
      (node (ref "C21") (pin "1") (pinfunction "1_1") (pintype "passive"))
      (node (ref "C22") (pin "2") (pinfunction "2_2") (pintype "passive"))
      (node (ref "C27") (pin "1") (pinfunction "1_1") (pintype "passive"))
      (node (ref "C41") (pin "1") (pinfunction "1_1") (pintype "passive"))
      (node (ref "C42") (pin "2") (pinfunction "2_2") (pintype "passive"))
      (node (ref "C43") (pin "1") (pinfunction "1_1") (pintype "passive"))
      (node (ref "D1") (pin "1") (pinfunction "A_1") (pintype "passive"))
      (node (ref "GSM_UART") (pin "5") (pinfunction "5_5") (pintype "passive"))
      (node (ref "JTAG") (pin "9") (pinfunction "9_9") (pintype "passive"))
      (node (ref "LCD") (pin "1") (pinfunction "VSS_1") (pintype "passive"))
      (node (ref "LCD") (pin "20") (pinfunction "LED_K_20") (pintype "passive"))
      (node (ref "NFC_SPI") (pin "9") (pinfunction "9_9") (pintype "passive"))
      (node (ref "Q1") (pin "3") (pinfunction "E_3") (pintype "passive"))
      (node (ref "Q2") (pin "3") (pinfunction "E_3") (pintype "passive"))
      (node (ref "Q3") (pin "3") (pinfunction "E_3") (pintype "passive"))
      (node (ref "R12") (pin "3") (pinfunction "BOT_3") (pintype "passive"))
      (node (ref "R20") (pin "2") (pinfunction "2_2") (pintype "passive"))
      (node (ref "R40") (pin "2") (pinfunction "2_2") (pintype "passive"))
      (node (ref "RESET") (pin "2") (pinfunction "2_2") (pintype "passive"))
      (node (ref "S1") (pin "6") (pinfunction "6_6") (pintype "passive"))
      (node (ref "U2") (pin "1") (pinfunction "A0_1") (pintype "passive"))
      (node (ref "U2") (pin "2") (pinfunction "A1_2") (pintype "passive"))
      (node (ref "U2") (pin "3") (pinfunction "A2_3") (pintype "passive"))
      (node (ref "U2") (pin "4") (pinfunction "GND_4") (pintype "passive"))
      (node (ref "U3") (pin "1") (pinfunction "GND_1") (pintype "passive"))
      (node (ref "U4") (pin "62") (pinfunction "AVss_62") (pintype "power_in"))
      (node (ref "U4") (pin "63") (pinfunction "DVss_63") (pintype "power_in"))
      (node (ref "U6") (pin "3") (pinfunction "GND_3") (pintype "passive"))
      (node (ref "USB") (pin "4") (pinfunction "4_4") (pintype "passive"))
      (node (ref "USB_UART") (pin "3") (pinfunction "3_3") (pintype "passive"))
    )
    (net (code "60") (name "Net-(BEEP1-A)") (class "Default")
      (node (ref "BEEP1") (pin "2") (pinfunction "A_2") (pintype "passive"))
      (node (ref "R21") (pin "1") (pinfunction "1_1") (pintype "passive"))
    )
    (net (code "61") (name "Net-(F1-Pad1)") (class "Default")
      (node (ref "F1") (pin "1") (pinfunction "1_1") (pintype "passive"))
      (node (ref "S1") (pin "3") (pinfunction "3_3") (pintype "passive"))
    )
    (net (code "62") (name "Net-(LCD-VO)") (class "Default")
      (node (ref "LCD") (pin "3") (pinfunction "VO_3") (pintype "passive"))
      (node (ref "R12") (pin "2") (pinfunction "TAP_2") (pintype "passive"))
    )
    (net (code "63") (name "Net-(LED2-K)") (class "Default")
      (node (ref "LED2") (pin "2") (pinfunction "K_2") (pintype "passive"))
      (node (ref "R20") (pin "1") (pinfunction "1_1") (pintype "passive"))
    )
    (net (code "64") (name "Net-(LED3-K)") (class "Default")
      (node (ref "LED3") (pin "2") (pinfunction "K_2") (pintype "passive"))
      (node (ref "R22") (pin "1") (pinfunction "1_1") (pintype "passive"))
    )
    (net (code "65") (name "Net-(LED4-K)") (class "Default")
      (node (ref "LED4") (pin "2") (pinfunction "K_2") (pintype "passive"))
      (node (ref "R23") (pin "1") (pinfunction "1_1") (pintype "passive"))
    )
    (net (code "66") (name "Net-(POWER1-Pad1)") (class "Default")
      (node (ref "POWER1") (pin "1") (pinfunction "1_1") (pintype "power_in"))
      (node (ref "S1") (pin "1") (pinfunction "1_1") (pintype "passive"))
    )
    (net (code "67") (name "Net-(POWER1-Pad2)") (class "Default")
      (node (ref "POWER1") (pin "2") (pinfunction "2_2") (pintype "power_in"))
      (node (ref "S1") (pin "4") (pinfunction "4_4") (pintype "passive"))
    )
    (net (code "68") (name "Net-(Q1-B)") (class "Default")
      (node (ref "Q1") (pin "2") (pinfunction "B_2") (pintype "passive"))
      (node (ref "R24") (pin "2") (pinfunction "2_2") (pintype "passive"))
    )
    (net (code "69") (name "Net-(Q1-C)") (class "Default")
      (node (ref "Q1") (pin "1") (pinfunction "C_1") (pintype "passive"))
      (node (ref "R21") (pin "2") (pinfunction "2_2") (pintype "passive"))
    )
    (net (code "70") (name "Net-(Q2-B)") (class "Default")
      (node (ref "Q2") (pin "2") (pinfunction "B_2") (pintype "passive"))
      (node (ref "R25") (pin "2") (pinfunction "2_2") (pintype "passive"))
    )
    (net (code "71") (name "Net-(Q2-C)") (class "Default")
      (node (ref "Q2") (pin "1") (pinfunction "C_1") (pintype "passive"))
      (node (ref "R22") (pin "2") (pinfunction "2_2") (pintype "passive"))
    )
    (net (code "72") (name "Net-(Q3-B)") (class "Default")
      (node (ref "Q3") (pin "2") (pinfunction "B_2") (pintype "passive"))
      (node (ref "R26") (pin "2") (pinfunction "2_2") (pintype "passive"))
    )
    (net (code "73") (name "Net-(Q3-C)") (class "Default")
      (node (ref "Q3") (pin "1") (pinfunction "C_1") (pintype "passive"))
      (node (ref "R23") (pin "2") (pinfunction "2_2") (pintype "passive"))
    )
    (net (code "74") (name "Net-(U6-VDD)") (class "Default")
      (node (ref "C41") (pin "2") (pinfunction "2_2") (pintype "passive"))
      (node (ref "R39") (pin "1") (pinfunction "1_1") (pintype "passive"))
      (node (ref "U6") (pin "6") (pinfunction "VDD_6") (pintype "passive"))
    )
    (net (code "75") (name "Net-(U6-~{RST})") (class "Default")
      (node (ref "R39") (pin "2") (pinfunction "2_2") (pintype "passive"))
      (node (ref "U6") (pin "9") (pinfunction "~{RST}_9") (pintype "passive"))
    )
    (net (code "76") (name "Net-(U6-~{SUBPEND})") (class "Default")
      (node (ref "R40") (pin "1") (pinfunction "1_1") (pintype "passive"))
      (node (ref "U6") (pin "11") (pinfunction "~{SUBPEND}_11") (pintype "passive"))
    )
    (net (code "77") (name "VCC-3.3V") (class "Default")
      (node (ref "C27") (pin "2") (pinfunction "2_2") (pintype "passive"))
      (node (ref "D2") (pin "2") (pinfunction "K_2") (pintype "passive"))
      (node (ref "GSM_UART") (pin "2") (pinfunction "2_2") (pintype "passive"))
      (node (ref "JTAG") (pin "2") (pinfunction "2_2") (pintype "passive"))
      (node (ref "LCD") (pin "2") (pinfunction "VDD_2") (pintype "passive"))
      (node (ref "LED2") (pin "1") (pinfunction "A_1") (pintype "passive"))
      (node (ref "NFC_SPI") (pin "1") (pinfunction "1_1") (pintype "passive"))
      (node (ref "R12") (pin "1") (pinfunction "TOP_1") (pintype "passive"))
      (node (ref "R19") (pin "2") (pinfunction "2_2") (pintype "passive"))
      (node (ref "U3") (pin "2") (pinfunction "OUT_2") (pintype "power_in"))
      (node (ref "U3") (pin "4") (pinfunction "OUT_4") (pintype "power_in"))
      (node (ref "U4") (pin "1") (pinfunction "DVcc_1") (pintype "power_in"))
      (node (ref "U4") (pin "64") (pinfunction "AVcc_64") (pintype "power_in"))
    )
    (net (code "78") (name "VCC-5V") (class "Default")
      (node (ref "BEEP1") (pin "1") (pinfunction "B_1") (pintype "passive"))
      (node (ref "C11") (pin "2") (pinfunction "2_2") (pintype "passive"))
      (node (ref "C20") (pin "1") (pinfunction "1_1") (pintype "passive"))
      (node (ref "C21") (pin "2") (pinfunction "2_2") (pintype "passive"))
      (node (ref "D1") (pin "2") (pinfunction "K_2") (pintype "passive"))
      (node (ref "F1") (pin "2") (pinfunction "2_2") (pintype "passive"))
      (node (ref "GSM_UART") (pin "1") (pinfunction "1_1") (pintype "passive"))
      (node (ref "LCD") (pin "19") (pinfunction "LED_A_19") (pintype "passive"))
      (node (ref "LED3") (pin "1") (pinfunction "A_1") (pintype "passive"))
      (node (ref "LED4") (pin "1") (pinfunction "A_1") (pintype "passive"))
      (node (ref "U2") (pin "8") (pinfunction "VCC_8") (pintype "passive"))
      (node (ref "U3") (pin "3") (pinfunction "IN_3") (pintype "input"))
    )
    (net (code "79") (name "VCCUSB") (class "Default")
      (node (ref "C42") (pin "1") (pinfunction "1_1") (pintype "passive"))
      (node (ref "C43") (pin "2") (pinfunction "2_2") (pintype "passive"))
      (node (ref "U6") (pin "7") (pinfunction "REGIN_7") (pintype "passive"))
      (node (ref "U6") (pin "8") (pinfunction "VBUS_8") (pintype "passive"))
      (node (ref "USB") (pin "1") (pinfunction "1_1") (pintype "passive"))
    )
    (net (code "80") (name "unconnected-(JTAG-Pad4)") (class "Default")
      (node (ref "JTAG") (pin "4") (pinfunction "4_4") (pintype "passive+no_connect"))
    )
    (net (code "81") (name "unconnected-(JTAG-Pad6)") (class "Default")
      (node (ref "JTAG") (pin "6") (pinfunction "6_6") (pintype "passive+no_connect"))
    )
    (net (code "82") (name "unconnected-(JTAG-Pad8)") (class "Default")
      (node (ref "JTAG") (pin "8") (pinfunction "8_8") (pintype "passive+no_connect"))
    )
    (net (code "83") (name "unconnected-(JTAG-Pad10)") (class "Default")
      (node (ref "JTAG") (pin "10") (pinfunction "10_10") (pintype "passive+no_connect"))
    )
    (net (code "84") (name "unconnected-(JTAG-Pad12)") (class "Default")
      (node (ref "JTAG") (pin "12") (pinfunction "12_12") (pintype "passive+no_connect"))
    )
    (net (code "85") (name "unconnected-(JTAG-Pad13)") (class "Default")
      (node (ref "JTAG") (pin "13") (pinfunction "13_13") (pintype "passive+no_connect"))
    )
    (net (code "86") (name "unconnected-(JTAG-Pad14)") (class "Default")
      (node (ref "JTAG") (pin "14") (pinfunction "14_14") (pintype "passive+no_connect"))
    )
    (net (code "87") (name "unconnected-(LCD-NC-Pad16)") (class "Default")
      (node (ref "LCD") (pin "16") (pinfunction "NC_16") (pintype "passive+no_connect"))
    )
    (net (code "88") (name "unconnected-(LCD-NC-Pad18)") (class "Default")
      (node (ref "LCD") (pin "18") (pinfunction "NC_18") (pintype "passive+no_connect"))
    )
    (net (code "89") (name "unconnected-(S1-Pad2)") (class "Default")
      (node (ref "S1") (pin "2") (pinfunction "2_2") (pintype "passive+no_connect"))
    )
    (net (code "90") (name "unconnected-(S1-Pad5)") (class "Default")
      (node (ref "S1") (pin "5") (pinfunction "5_5") (pintype "passive+no_connect"))
    )
    (net (code "91") (name "unconnected-(U2-WP-Pad7)") (class "Default")
      (node (ref "U2") (pin "7") (pinfunction "WP_7") (pintype "passive+no_connect"))
    )
    (net (code "92") (name "unconnected-(U4-P3.0{slash}STE0-Pad28)") (class "Default")
      (node (ref "U4") (pin "28") (pinfunction "P3.0/STE0_28") (pintype "power_in+no_connect"))
    )
    (net (code "93") (name "unconnected-(U4-P3.1{slash}SIMO0-Pad29)") (class "Default")
      (node (ref "U4") (pin "29") (pinfunction "P3.1/SIMO0_29") (pintype "power_in+no_connect"))
    )
    (net (code "94") (name "unconnected-(U4-P3.2{slash}SOMI1-Pad30)") (class "Default")
      (node (ref "U4") (pin "30") (pinfunction "P3.2/SOMI1_30") (pintype "power_in+no_connect"))
    )
    (net (code "95") (name "unconnected-(U4-P3.3{slash}UCLK0-Pad31)") (class "Default")
      (node (ref "U4") (pin "31") (pinfunction "P3.3/UCLK0_31") (pintype "power_in+no_connect"))
    )
    (net (code "96") (name "unconnected-(U4-P4.2{slash}TB2-Pad38)") (class "Default")
      (node (ref "U4") (pin "38") (pinfunction "P4.2/TB2_38") (pintype "power_in+no_connect"))
    )
    (net (code "97") (name "unconnected-(U4-P4.3{slash}TB3-Pad39)") (class "Default")
      (node (ref "U4") (pin "39") (pinfunction "P4.3/TB3_39") (pintype "power_in+no_connect"))
    )
    (net (code "98") (name "unconnected-(U4-P4.4{slash}TB4-Pad40)") (class "Default")
      (node (ref "U4") (pin "40") (pinfunction "P4.4/TB4_40") (pintype "power_in+no_connect"))
    )
    (net (code "99") (name "unconnected-(U4-P5.4{slash}MCLK-Pad48)") (class "Default")
      (node (ref "U4") (pin "48") (pinfunction "P5.4/MCLK_48") (pintype "power_in+no_connect"))
    )
    (net (code "100") (name "unconnected-(U4-P5.5{slash}SMCLK-Pad49)") (class "Default")
      (node (ref "U4") (pin "49") (pinfunction "P5.5/SMCLK_49") (pintype "power_in+no_connect"))
    )
    (net (code "101") (name "unconnected-(U4-P5.6{slash}ACLK-Pad50)") (class "Default")
      (node (ref "U4") (pin "50") (pinfunction "P5.6/ACLK_50") (pintype "power_in+no_connect"))
    )
    (net (code "102") (name "unconnected-(U4-P5.7{slash}TBoutH-Pad51)") (class "Default")
      (node (ref "U4") (pin "51") (pinfunction "P5.7/TBoutH_51") (pintype "power_in+no_connect"))
    )
    (net (code "103") (name "unconnected-(U4-VREF+-Pad7)") (class "Default")
      (node (ref "U4") (pin "7") (pinfunction "VREF+_7") (pintype "power_in+no_connect"))
    )
    (net (code "104") (name "unconnected-(U4-VREF-{slash}VeREF--Pad11)") (class "Default")
      (node (ref "U4") (pin "11") (pinfunction "VREF-/VeREF-_11") (pintype "power_in+no_connect"))
    )
    (net (code "105") (name "unconnected-(U4-VeREF+-Pad10)") (class "Default")
      (node (ref "U4") (pin "10") (pinfunction "VeREF+_10") (pintype "power_in+no_connect"))
    )
    (net (code "106") (name "unconnected-(U4-XIN-Pad8)") (class "Default")
      (node (ref "U4") (pin "8") (pinfunction "XIN_8") (pintype "power_in+no_connect"))
    )
    (net (code "107") (name "unconnected-(U4-XOUT{slash}TCLK-Pad9)") (class "Default")
      (node (ref "U4") (pin "9") (pinfunction "XOUT/TCLK_9") (pintype "power_in+no_connect"))
    )
    (net (code "108") (name "unconnected-(U4-XT2IN-Pad53)") (class "Default")
      (node (ref "U4") (pin "53") (pinfunction "XT2IN_53") (pintype "power_in+no_connect"))
    )
    (net (code "109") (name "unconnected-(U4-XT2OUT-Pad52)") (class "Default")
      (node (ref "U4") (pin "52") (pinfunction "XT2OUT_52") (pintype "power_in+no_connect"))
    )
    (net (code "110") (name "unconnected-(U6-Pad10)") (class "Default")
      (node (ref "U6") (pin "10") (pinfunction "10_10") (pintype "passive+no_connect"))
    )
    (net (code "111") (name "unconnected-(U6-Pad13)") (class "Default")
      (node (ref "U6") (pin "13") (pinfunction "13_13") (pintype "passive+no_connect"))
    )
    (net (code "112") (name "unconnected-(U6-Pad14)") (class "Default")
      (node (ref "U6") (pin "14") (pinfunction "14_14") (pintype "passive+no_connect"))
    )
    (net (code "113") (name "unconnected-(U6-Pad15)") (class "Default")
      (node (ref "U6") (pin "15") (pinfunction "15_15") (pintype "passive+no_connect"))
    )
    (net (code "114") (name "unconnected-(U6-Pad16)") (class "Default")
      (node (ref "U6") (pin "16") (pinfunction "16_16") (pintype "passive+no_connect"))
    )
    (net (code "115") (name "unconnected-(U6-Pad17)") (class "Default")
      (node (ref "U6") (pin "17") (pinfunction "17_17") (pintype "passive+no_connect"))
    )
    (net (code "116") (name "unconnected-(U6-Pad18)") (class "Default")
      (node (ref "U6") (pin "18") (pinfunction "18_18") (pintype "passive+no_connect"))
    )
    (net (code "117") (name "unconnected-(U6-Pad19)") (class "Default")
      (node (ref "U6") (pin "19") (pinfunction "19_19") (pintype "passive+no_connect"))
    )
    (net (code "118") (name "unconnected-(U6-Pad20)") (class "Default")
      (node (ref "U6") (pin "20") (pinfunction "20_20") (pintype "passive+no_connect"))
    )
    (net (code "119") (name "unconnected-(U6-Pad21)") (class "Default")
      (node (ref "U6") (pin "21") (pinfunction "21_21") (pintype "passive+no_connect"))
    )
    (net (code "120") (name "unconnected-(U6-Pad22)") (class "Default")
      (node (ref "U6") (pin "22") (pinfunction "22_22") (pintype "passive+no_connect"))
    )
    (net (code "121") (name "unconnected-(U6-SUBPEND-Pad12)") (class "Default")
      (node (ref "U6") (pin "12") (pinfunction "SUBPEND_12") (pintype "passive+no_connect"))
    )
    (net (code "122") (name "unconnected-(USB-Pad5)") (class "Default")
      (node (ref "USB") (pin "5") (pinfunction "5_5") (pintype "passive+no_connect"))
    )
  )
)
